# Sheet_1_2021-06-19.net
KiCad netlist of a schematic drawn in Altium Designer
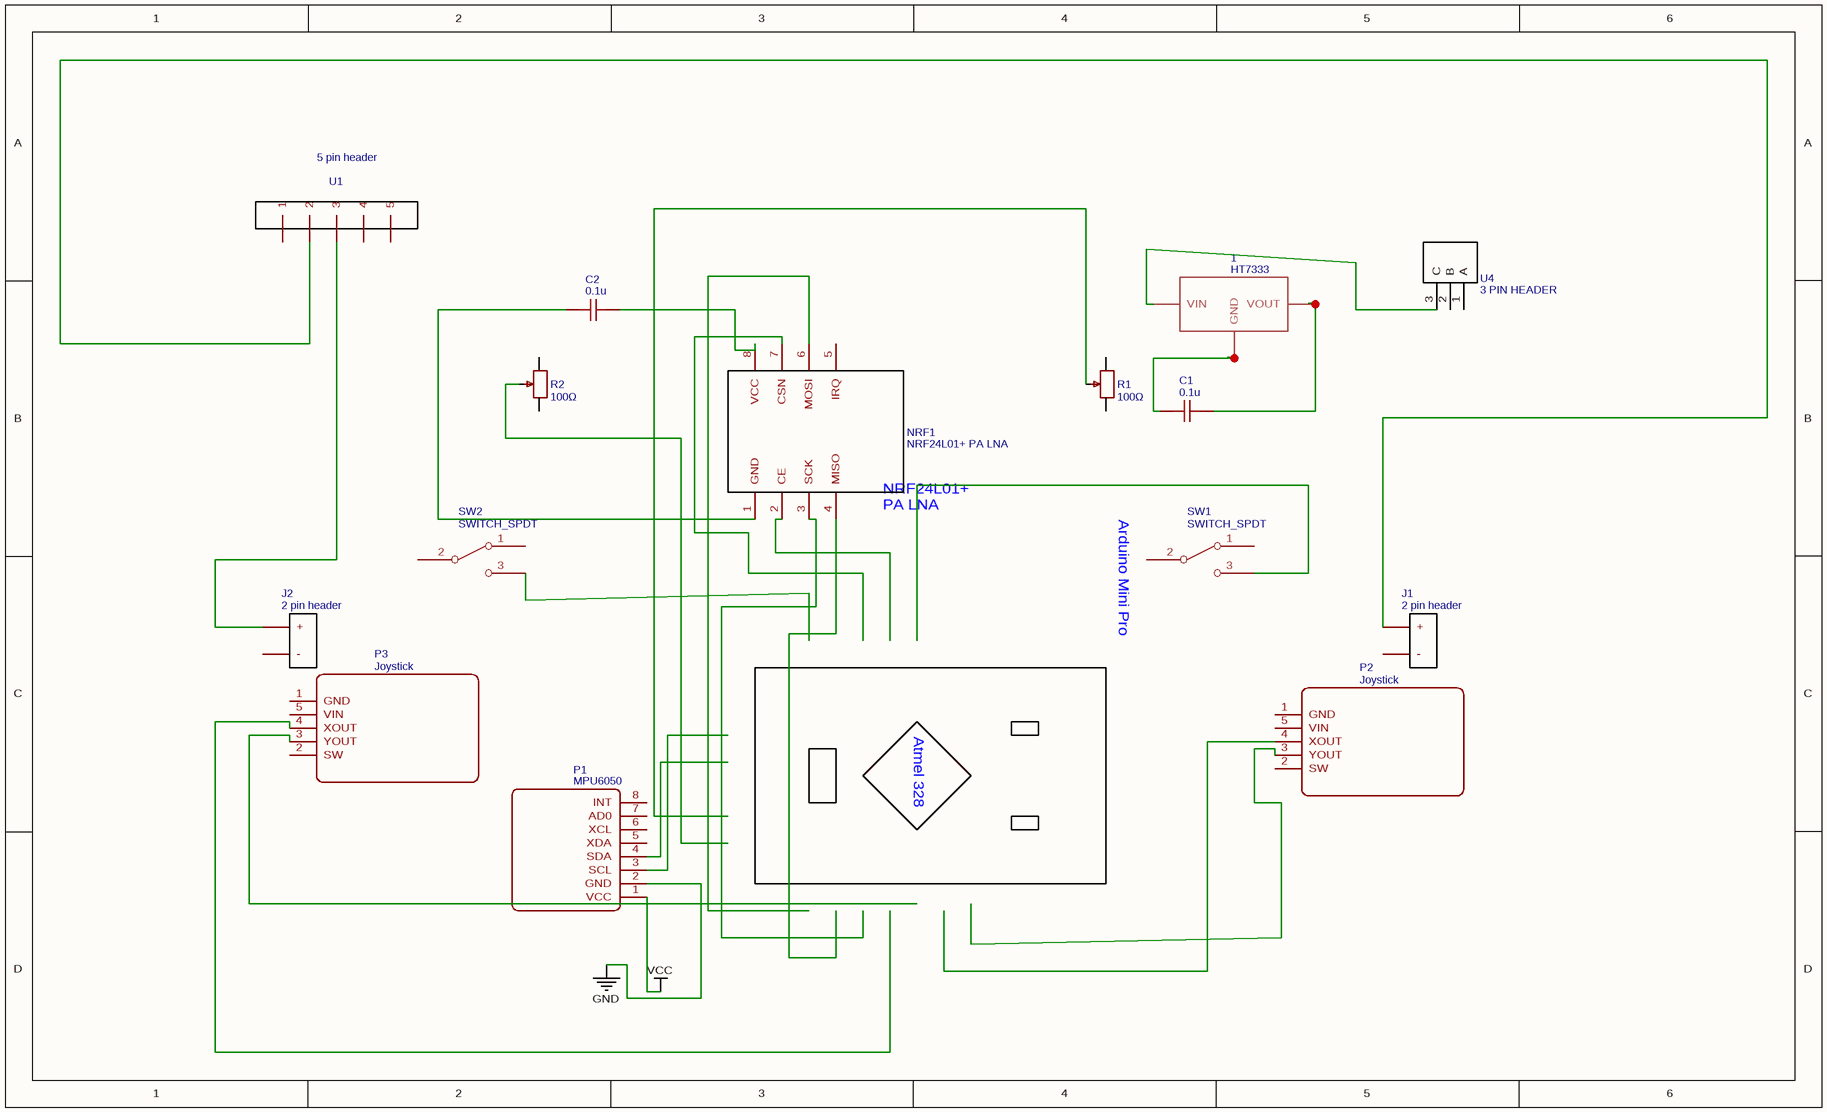
[diagram p0: Sheet_1_2021-06-19.schdoc]

(export (version "E")
  (design (tool "Eeschema 10.0.6"))
  (components
    (comp (ref "1")
      (value "HT7333")
      (fields (field (name "CONTRIBUTOR") "jay chauhan"))
      (libsource (lib "altium-import") (part "root_0_HT7333_"))
    )
    (comp (ref "C1")
      (value "0.1u")
      (fields (field (name "CONTRIBUTOR") "LCEDA_Lib"))
      (libsource (lib "altium-import") (part "root_0_0.1u_"))
    )
    (comp (ref "C2")
      (value "0.1u")
      (fields (field (name "CONTRIBUTOR") "LCEDA_Lib"))
      (libsource (lib "altium-import") (part "root_0_0.1u_"))
    )
    (comp (ref "J1")
      (value "2 pin header")
      (fields (field (name "CONTRIBUTOR") "tcirineo"))
      (libsource (lib "altium-import") (part "root_0_2 pin header_"))
    )
    (comp (ref "J2")
      (value "2 pin header")
      (fields (field (name "CONTRIBUTOR") "tcirineo"))
      (libsource (lib "altium-import") (part "root_0_2 pin header_"))
    )
    (comp (ref "NRF1")
      (value "NRF24L01+ PA LNA")
      (fields (field (name "BOM_SUPPLIER PART") "NRF24L01p-PA-LNA") (field (name "CONTRIBUTOR") "irukard"))
      (libsource (lib "altium-import") (part "root_1_NRF24L01+ PA LNA_"))
    )
    (comp (ref "P1")
      (value "MPU6050")
      (fields (field (name "CONTRIBUTOR") "Mr. Sandman"))
      (libsource (lib "altium-import") (part "root_2_MPU6050_"))
    )
    (comp (ref "P2")
      (value "Joystick")
      (fields (field (name "CONTRIBUTOR") "shubham kumar"))
      (libsource (lib "altium-import") (part "root_0_Joystick_"))
    )
    (comp (ref "P3")
      (value "Joystick")
      (fields (field (name "CONTRIBUTOR") "shubham kumar"))
      (libsource (lib "altium-import") (part "root_0_Joystick_"))
    )
    (comp (ref "R1")
      (value "100Ω")
      (fields (field (name "BOM_MANUFACTURER PART") "Precision potentiometer100Ω"))
      (libsource (lib "altium-import") (part "root_0_100Ω_"))
    )
    (comp (ref "R2")
      (value "100Ω")
      (fields (field (name "BOM_MANUFACTURER PART") "Precision potentiometer100Ω"))
      (libsource (lib "altium-import") (part "root_0_100Ω_"))
    )
    (comp (ref "SW1") (value "SWITCH_SPDT") (libsource (lib "altium-import") (part "root_0_SWITCH_SPDT_")))
    (comp (ref "SW2") (value "SWITCH_SPDT") (libsource (lib "altium-import") (part "root_0_SWITCH_SPDT_")))
    (comp (ref "U1")
      (value "5 pin header")
      (fields (field (name "CONTRIBUTOR") "alberto.perez.madruga"))
      (libsource (lib "altium-import") (part "root_1_5 pin header_"))
    )
    (comp (ref "U4")
      (value "3 PIN HEADER")
      (fields (field (name "BOM_MANUFACTURER PART") "3 pin header") (field (name "CONTRIBUTOR") "Deimoss"))
      (libsource (lib "altium-import") (part "root_3_3 PIN HEADER_"))
    )
  )
  (nets
    (net (code "1") (name "GND") (class "Default")
      (node (ref "P1") (pin "2") (pinfunction "GND_2") (pintype "passive"))
    )
    (net (code "2") (name "Net-(1-PadGND)") (class "Default")
      (node (ref "1") (pin "GND") (pinfunction "GND_GND") (pintype "passive"))
      (node (ref "C1") (pin "1") (pinfunction "1_1") (pintype "passive"))
    )
    (net (code "3") (name "Net-(1-PadVOUT)") (class "Default")
      (node (ref "1") (pin "VOUT") (pinfunction "VOUT_VOUT") (pintype "passive"))
      (node (ref "C1") (pin "2") (pinfunction "2_2") (pintype "passive"))
    )
    (net (code "4") (name "Net-(J1-+)") (class "Default")
      (node (ref "J1") (pin "1") (pinfunction "+_1") (pintype "passive"))
      (node (ref "U1") (pin "2") (pinfunction "2_2") (pintype "passive"))
    )
    (net (code "5") (name "Net-(J2-+)") (class "Default")
      (node (ref "J2") (pin "1") (pinfunction "+_1") (pintype "passive"))
      (node (ref "U1") (pin "3") (pinfunction "3_3") (pintype "passive"))
    )
    (net (code "6") (name "Net-(NRF1-GND)") (class "Default")
      (node (ref "C2") (pin "1") (pinfunction "1_1") (pintype "passive"))
      (node (ref "NRF1") (pin "1") (pinfunction "GND_1") (pintype "passive"))
    )
    (net (code "7") (name "Net-(NRF1-VCC)") (class "Default")
      (node (ref "C2") (pin "2") (pinfunction "2_2") (pintype "passive"))
      (node (ref "NRF1") (pin "8") (pinfunction "VCC_8") (pintype "passive"))
    )
    (net (code "8") (name "Net-(U4-C)") (class "Default")
      (node (ref "1") (pin "VIN") (pinfunction "VIN_VIN") (pintype "passive"))
      (node (ref "U4") (pin "3") (pinfunction "C_3") (pintype "passive"))
    )
    (net (code "9") (name "VCC") (class "Default")
      (node (ref "P1") (pin "1") (pinfunction "VCC_1") (pintype "passive"))
    )
    (net (code "10") (name "unconnected-(J1---Pad2)") (class "Default")
      (node (ref "J1") (pin "2") (pinfunction "-_2") (pintype "passive"))
    )
    (net (code "11") (name "unconnected-(J2---Pad2)") (class "Default")
      (node (ref "J2") (pin "2") (pinfunction "-_2") (pintype "passive"))
    )
    (net (code "12") (name "unconnected-(NRF1-CE-Pad2)") (class "Default")
      (node (ref "NRF1") (pin "2") (pinfunction "CE_2") (pintype "passive"))
    )
    (net (code "13") (name "unconnected-(NRF1-CSN-Pad7)") (class "Default")
      (node (ref "NRF1") (pin "7") (pinfunction "CSN_7") (pintype "passive"))
    )
    (net (code "14") (name "unconnected-(NRF1-IRQ-Pad5)") (class "Default")
      (node (ref "NRF1") (pin "5") (pinfunction "IRQ_5") (pintype "passive"))
    )
    (net (code "15") (name "unconnected-(NRF1-MISO-Pad4)") (class "Default")
      (node (ref "NRF1") (pin "4") (pinfunction "MISO_4") (pintype "passive"))
    )
    (net (code "16") (name "unconnected-(NRF1-MOSI-Pad6)") (class "Default")
      (node (ref "NRF1") (pin "6") (pinfunction "MOSI_6") (pintype "passive"))
    )
    (net (code "17") (name "unconnected-(NRF1-SCK-Pad3)") (class "Default")
      (node (ref "NRF1") (pin "3") (pinfunction "SCK_3") (pintype "passive"))
    )
    (net (code "18") (name "unconnected-(P1-AD0-Pad7)") (class "Default")
      (node (ref "P1") (pin "7") (pinfunction "AD0_7") (pintype "passive"))
    )
    (net (code "19") (name "unconnected-(P1-INT-Pad8)") (class "Default")
      (node (ref "P1") (pin "8") (pinfunction "INT_8") (pintype "passive"))
    )
    (net (code "20") (name "unconnected-(P1-SCL-Pad3)") (class "Default")
      (node (ref "P1") (pin "3") (pinfunction "SCL_3") (pintype "passive"))
    )
    (net (code "21") (name "unconnected-(P1-SDA-Pad4)") (class "Default")
      (node (ref "P1") (pin "4") (pinfunction "SDA_4") (pintype "passive"))
    )
    (net (code "22") (name "unconnected-(P1-XCL-Pad6)") (class "Default")
      (node (ref "P1") (pin "6") (pinfunction "XCL_6") (pintype "passive"))
    )
    (net (code "23") (name "unconnected-(P1-XDA-Pad5)") (class "Default")
      (node (ref "P1") (pin "5") (pinfunction "XDA_5") (pintype "passive"))
    )
    (net (code "24") (name "unconnected-(P2-GND-Pad1)") (class "Default")
      (node (ref "P2") (pin "1") (pinfunction "GND_1") (pintype "passive"))
    )
    (net (code "25") (name "unconnected-(P2-SW-Pad2)") (class "Default")
      (node (ref "P2") (pin "2") (pinfunction "SW_2") (pintype "passive"))
    )
    (net (code "26") (name "unconnected-(P2-VIN-Pad5)") (class "Default")
      (node (ref "P2") (pin "5") (pinfunction "VIN_5") (pintype "passive"))
    )
    (net (code "27") (name "unconnected-(P2-XOUT-Pad4)") (class "Default")
      (node (ref "P2") (pin "4") (pinfunction "XOUT_4") (pintype "passive"))
    )
    (net (code "28") (name "unconnected-(P2-YOUT-Pad3)") (class "Default")
      (node (ref "P2") (pin "3") (pinfunction "YOUT_3") (pintype "passive"))
    )
    (net (code "29") (name "unconnected-(P3-GND-Pad1)") (class "Default")
      (node (ref "P3") (pin "1") (pinfunction "GND_1") (pintype "passive"))
    )
    (net (code "30") (name "unconnected-(P3-SW-Pad2)") (class "Default")
      (node (ref "P3") (pin "2") (pinfunction "SW_2") (pintype "passive"))
    )
    (net (code "31") (name "unconnected-(P3-VIN-Pad5)") (class "Default")
      (node (ref "P3") (pin "5") (pinfunction "VIN_5") (pintype "passive"))
    )
    (net (code "32") (name "unconnected-(P3-XOUT-Pad4)") (class "Default")
      (node (ref "P3") (pin "4") (pinfunction "XOUT_4") (pintype "passive"))
    )
    (net (code "33") (name "unconnected-(P3-YOUT-Pad3)") (class "Default")
      (node (ref "P3") (pin "3") (pinfunction "YOUT_3") (pintype "passive"))
    )
    (net (code "34") (name "unconnected-(R1-Pad1)") (class "Default")
      (node (ref "R1") (pin "1") (pinfunction "1_1") (pintype "passive"))
    )
    (net (code "35") (name "unconnected-(R1-Pad2)") (class "Default")
      (node (ref "R1") (pin "2") (pinfunction "2_2") (pintype "passive"))
    )
    (net (code "36") (name "unconnected-(R1-Pad3)") (class "Default")
      (node (ref "R1") (pin "3") (pinfunction "3_3") (pintype "passive"))
    )
    (net (code "37") (name "unconnected-(R2-Pad1)") (class "Default")
      (node (ref "R2") (pin "1") (pinfunction "1_1") (pintype "passive"))
    )
    (net (code "38") (name "unconnected-(R2-Pad2)") (class "Default")
      (node (ref "R2") (pin "2") (pinfunction "2_2") (pintype "passive"))
    )
    (net (code "39") (name "unconnected-(R2-Pad3)") (class "Default")
      (node (ref "R2") (pin "3") (pinfunction "3_3") (pintype "passive"))
    )
    (net (code "40") (name "unconnected-(SW1-Pad1)") (class "Default")
      (node (ref "SW1") (pin "1") (pinfunction "1_1") (pintype "passive"))
    )
    (net (code "41") (name "unconnected-(SW1-Pad2)") (class "Default")
      (node (ref "SW1") (pin "2") (pinfunction "2_2") (pintype "passive"))
    )
    (net (code "42") (name "unconnected-(SW1-Pad3)") (class "Default")
      (node (ref "SW1") (pin "3") (pinfunction "3_3") (pintype "passive"))
    )
    (net (code "43") (name "unconnected-(SW2-Pad1)") (class "Default")
      (node (ref "SW2") (pin "1") (pinfunction "1_1") (pintype "passive"))
    )
    (net (code "44") (name "unconnected-(SW2-Pad2)") (class "Default")
      (node (ref "SW2") (pin "2") (pinfunction "2_2") (pintype "passive"))
    )
    (net (code "45") (name "unconnected-(SW2-Pad3)") (class "Default")
      (node (ref "SW2") (pin "3") (pinfunction "3_3") (pintype "passive"))
    )
    (net (code "46") (name "unconnected-(U1-Pad1)") (class "Default")
      (node (ref "U1") (pin "1") (pinfunction "1_1") (pintype "passive"))
    )
    (net (code "47") (name "unconnected-(U1-Pad4)") (class "Default")
      (node (ref "U1") (pin "4") (pinfunction "4_4") (pintype "passive"))
    )
    (net (code "48") (name "unconnected-(U1-Pad5)") (class "Default")
      (node (ref "U1") (pin "5") (pinfunction "5_5") (pintype "passive"))
    )
    (net (code "49") (name "unconnected-(U4-A-Pad1)") (class "Default")
      (node (ref "U4") (pin "1") (pinfunction "A_1") (pintype "passive"))
    )
    (net (code "50") (name "unconnected-(U4-B-Pad2)") (class "Default")
      (node (ref "U4") (pin "2") (pinfunction "B_2") (pintype "passive"))
    )
  )
)
